# followLineMain.net
KiCad netlist of a schematic drawn in EAGLE
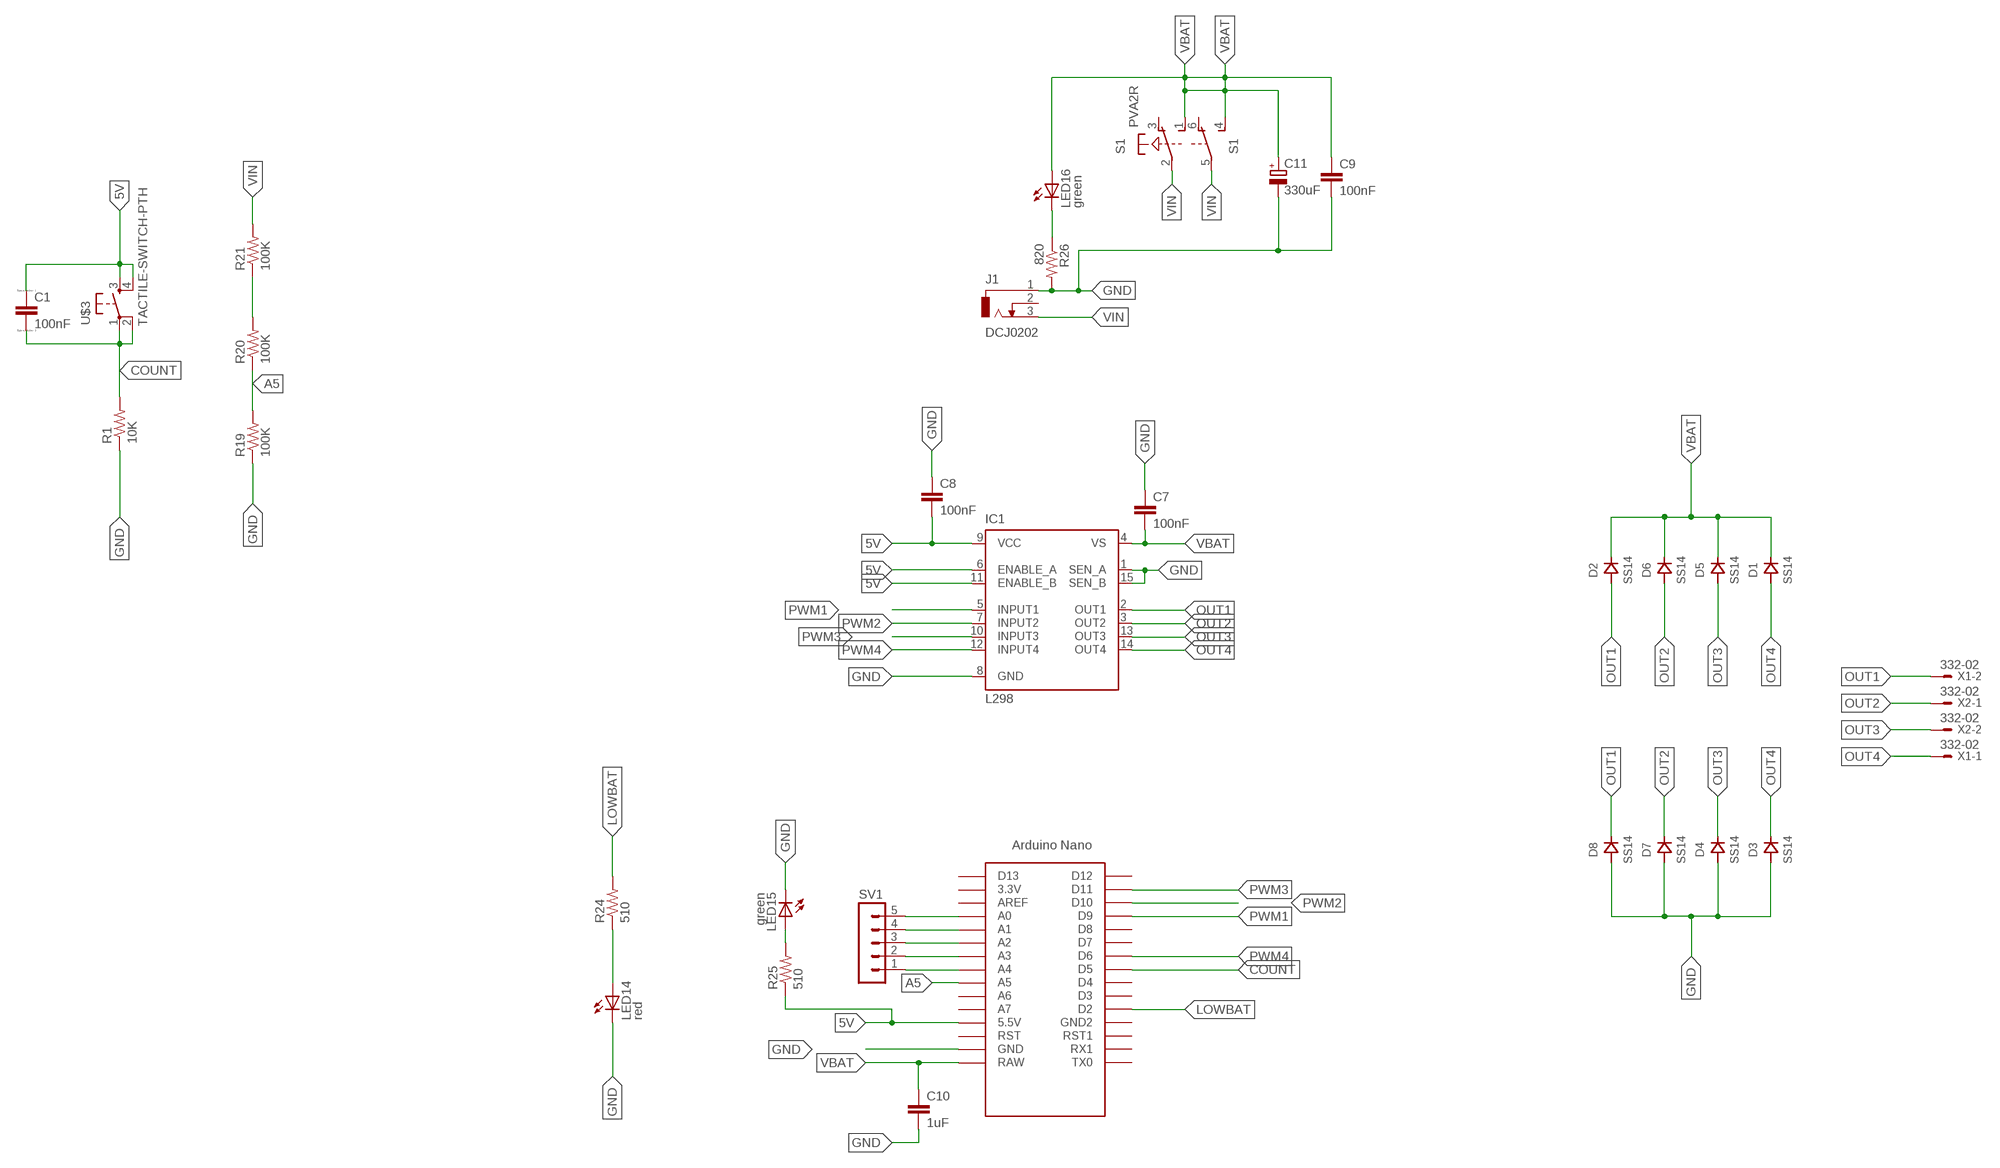
[diagram p0: schematic, sheet 1]

(export (version "E")
  (design (tool "Eeschema 10.0.6"))
  (components
    (comp (ref "C1")
      (value "100nF")
      (footprint "eagle-import:C0603")
      (libsource (lib "eagle-import") (part "CC0603"))
    )
    (comp (ref "C7")
      (value "100nF")
      (footprint "eagle-import:0805")
      (libsource (lib "eagle-import") (part "CAP0805"))
    )
    (comp (ref "C8")
      (value "100nF")
      (footprint "eagle-import:0805")
      (libsource (lib "eagle-import") (part "CAP0805"))
    )
    (comp (ref "C9")
      (value "100nF")
      (footprint "eagle-import:0805")
      (libsource (lib "eagle-import") (part "CAP0805"))
    )
    (comp (ref "C10")
      (value "1uF")
      (footprint "eagle-import:1206")
      (libsource (lib "eagle-import") (part "CAP1206"))
    )
    (comp (ref "C11")
      (value "330uF")
      (footprint "eagle-import:E5-13")
      (libsource (lib "eagle-import") (part "CPOL-EUE5-13"))
    )
    (comp (ref "D1")
      (value "SS14")
      (footprint "eagle-import:DO214")
      (libsource (lib "eagle-import") (part "SS14"))
    )
    (comp (ref "D2")
      (value "SS14")
      (footprint "eagle-import:DO214")
      (libsource (lib "eagle-import") (part "SS14"))
    )
    (comp (ref "D3")
      (value "SS14")
      (footprint "eagle-import:DO214")
      (libsource (lib "eagle-import") (part "SS14"))
    )
    (comp (ref "D4")
      (value "SS14")
      (footprint "eagle-import:DO214")
      (libsource (lib "eagle-import") (part "SS14"))
    )
    (comp (ref "D5")
      (value "SS14")
      (footprint "eagle-import:DO214")
      (libsource (lib "eagle-import") (part "SS14"))
    )
    (comp (ref "D6")
      (value "SS14")
      (footprint "eagle-import:DO214")
      (libsource (lib "eagle-import") (part "SS14"))
    )
    (comp (ref "D7")
      (value "SS14")
      (footprint "eagle-import:DO214")
      (libsource (lib "eagle-import") (part "SS14"))
    )
    (comp (ref "D8")
      (value "SS14")
      (footprint "eagle-import:DO214")
      (libsource (lib "eagle-import") (part "SS14"))
    )
    (comp (ref "IC1")
      (value "L298")
      (footprint "eagle-import:MULTIWATT-15")
      (fields (field (name "MPN") "L298N"))
      (libsource (lib "eagle-import") (part "L298"))
    )
    (comp (ref "J1")
      (value "DCJ0202")
      (footprint "eagle-import:DCJ0202")
      (libsource (lib "eagle-import") (part "DCJ0202"))
    )
    (comp (ref "LED14")
      (value "red")
      (footprint "eagle-import:SML0805")
      (libsource (lib "eagle-import") (part "LEDSML0805"))
    )
    (comp (ref "LED15")
      (value "green")
      (footprint "eagle-import:SML0805")
      (libsource (lib "eagle-import") (part "LEDSML0805"))
    )
    (comp (ref "LED16")
      (value "green")
      (footprint "eagle-import:SML0805")
      (libsource (lib "eagle-import") (part "LEDSML0805"))
    )
    (comp (ref "R1")
      (value "10K")
      (footprint "eagle-import:0805")
      (libsource (lib "eagle-import") (part "RESISTOR0805-RES"))
    )
    (comp (ref "R19")
      (value "100K")
      (footprint "eagle-import:0805")
      (libsource (lib "eagle-import") (part "RESISTOR0805-RES"))
    )
    (comp (ref "R20")
      (value "100K")
      (footprint "eagle-import:0805")
      (libsource (lib "eagle-import") (part "RESISTOR0805-RES"))
    )
    (comp (ref "R21")
      (value "100K")
      (footprint "eagle-import:0805")
      (libsource (lib "eagle-import") (part "RESISTOR0805-RES"))
    )
    (comp (ref "R24")
      (value "510")
      (footprint "eagle-import:0805")
      (libsource (lib "eagle-import") (part "RESISTOR0805-RES"))
    )
    (comp (ref "R25")
      (value "510")
      (footprint "eagle-import:0805")
      (libsource (lib "eagle-import") (part "RESISTOR0805-RES"))
    )
    (comp (ref "R26")
      (value "820")
      (footprint "eagle-import:0805")
      (libsource (lib "eagle-import") (part "RESISTOR0805-RES"))
    )
    (comp (ref "S1")
      (value "PVA2R")
      (footprint "eagle-import:PVA2R")
      (libsource (lib "eagle-import") (part "PVA2R"))
    )
    (comp (ref "SV1")
      (value "MA05-1")
      (footprint "eagle-import:MA05-1")
      (libsource (lib "eagle-import") (part "MA05-1"))
    )
    (comp (ref "U$1")
      (value "NANO")
      (footprint "eagle-import:NANO")
      (libsource (lib "eagle-import") (part "NANO"))
    )
    (comp (ref "U$3")
      (value "TACTILE-SWITCH-PTH")
      (footprint "eagle-import:TAC-SWITCH-PTH")
      (libsource (lib "eagle-import") (part "TACTILE-SWITCH-PTH"))
    )
    (comp (ref "X1")
      (value "332-02")
      (footprint "eagle-import:332-02")
      (libsource (lib "eagle-import") (part "332-02"))
    )
    (comp (ref "X2")
      (value "332-02")
      (footprint "eagle-import:332-02")
      (libsource (lib "eagle-import") (part "332-02"))
    )
  )
  (nets
    (net (code "1") (name "5V") (class "Default")
      (node (ref "C1") (pin "1") (pinfunction "1_1") (pintype "passive"))
      (node (ref "C8") (pin "2") (pinfunction "2_2") (pintype "passive"))
      (node (ref "IC1") (pin "11") (pinfunction "ENABLE_B_11") (pintype "input"))
      (node (ref "IC1") (pin "6") (pinfunction "ENABLE_A_6") (pintype "input"))
      (node (ref "IC1") (pin "9") (pinfunction "VCC_9") (pintype "power_in"))
      (node (ref "R25") (pin "1") (pinfunction "1_1") (pintype "passive"))
      (node (ref "U$1") (pin "5V") (pinfunction "5.5V_5V") (pintype "bidirectional"))
      (node (ref "U$3") (pin "3") (pinfunction "3_3") (pintype "passive"))
      (node (ref "U$3") (pin "4") (pinfunction "4_4") (pintype "passive"))
    )
    (net (code "2") (name "A5") (class "Default")
      (node (ref "R19") (pin "2") (pinfunction "2_2") (pintype "passive"))
      (node (ref "R20") (pin "1") (pinfunction "1_1") (pintype "passive"))
      (node (ref "U$1") (pin "A5") (pinfunction "A5_A5") (pintype "bidirectional"))
    )
    (net (code "3") (name "COUNT") (class "Default")
      (node (ref "C1") (pin "2") (pinfunction "2_2") (pintype "passive"))
      (node (ref "R1") (pin "2") (pinfunction "2_2") (pintype "passive"))
      (node (ref "U$1") (pin "D5") (pinfunction "D5_D5") (pintype "bidirectional"))
      (node (ref "U$3") (pin "1") (pinfunction "1_1") (pintype "passive"))
      (node (ref "U$3") (pin "2") (pinfunction "2_2") (pintype "passive"))
    )
    (net (code "4") (name "GND") (class "Default")
      (node (ref "C10") (pin "2") (pinfunction "2_2") (pintype "passive"))
      (node (ref "C11") (pin "-") (pinfunction "-_-") (pintype "passive"))
      (node (ref "C7") (pin "1") (pinfunction "1_1") (pintype "passive"))
      (node (ref "C8") (pin "1") (pinfunction "1_1") (pintype "passive"))
      (node (ref "C9") (pin "2") (pinfunction "2_2") (pintype "passive"))
      (node (ref "D3") (pin "ANODE") (pinfunction "ANODE_ANODE") (pintype "bidirectional"))
      (node (ref "D4") (pin "ANODE") (pinfunction "ANODE_ANODE") (pintype "bidirectional"))
      (node (ref "D7") (pin "ANODE") (pinfunction "ANODE_ANODE") (pintype "bidirectional"))
      (node (ref "D8") (pin "ANODE") (pinfunction "ANODE_ANODE") (pintype "bidirectional"))
      (node (ref "IC1") (pin "1") (pinfunction "SEN_A_1") (pintype "input"))
      (node (ref "IC1") (pin "15") (pinfunction "SEN_B_15") (pintype "input"))
      (node (ref "IC1") (pin "8") (pinfunction "GND_8") (pintype "power_in"))
      (node (ref "J1") (pin "1") (pinfunction "1_1") (pintype "passive"))
      (node (ref "LED14") (pin "C") (pinfunction "C_C") (pintype "passive"))
      (node (ref "LED15") (pin "C") (pinfunction "C_C") (pintype "passive"))
      (node (ref "R1") (pin "1") (pinfunction "1_1") (pintype "passive"))
      (node (ref "R19") (pin "1") (pinfunction "1_1") (pintype "passive"))
      (node (ref "R26") (pin "2") (pinfunction "2_2") (pintype "passive"))
      (node (ref "U$1") (pin "GND") (pinfunction "GND_GND") (pintype "bidirectional"))
    )
    (net (code "5") (name "LOWBAT") (class "Default")
      (node (ref "R24") (pin "2") (pinfunction "2_2") (pintype "passive"))
      (node (ref "U$1") (pin "D2") (pinfunction "D2_D2") (pintype "bidirectional"))
    )
    (net (code "6") (name "Net-(LED14-PadA)") (class "Default")
      (node (ref "LED14") (pin "A") (pinfunction "A_A") (pintype "passive"))
      (node (ref "R24") (pin "1") (pinfunction "1_1") (pintype "passive"))
    )
    (net (code "7") (name "Net-(LED15-PadA)") (class "Default")
      (node (ref "LED15") (pin "A") (pinfunction "A_A") (pintype "passive"))
      (node (ref "R25") (pin "2") (pinfunction "2_2") (pintype "passive"))
    )
    (net (code "8") (name "Net-(LED16-PadC)") (class "Default")
      (node (ref "LED16") (pin "C") (pinfunction "C_C") (pintype "passive"))
      (node (ref "R26") (pin "1") (pinfunction "1_1") (pintype "passive"))
    )
    (net (code "9") (name "Net-(R20-Pad2)") (class "Default")
      (node (ref "R20") (pin "2") (pinfunction "2_2") (pintype "passive"))
      (node (ref "R21") (pin "1") (pinfunction "1_1") (pintype "passive"))
    )
    (net (code "10") (name "Net-(SV1-Pad1)") (class "Default")
      (node (ref "SV1") (pin "1") (pinfunction "1_1") (pintype "passive"))
      (node (ref "U$1") (pin "A4") (pinfunction "A4_A4") (pintype "bidirectional"))
    )
    (net (code "11") (name "Net-(SV1-Pad2)") (class "Default")
      (node (ref "SV1") (pin "2") (pinfunction "2_2") (pintype "passive"))
      (node (ref "U$1") (pin "A3") (pinfunction "A3_A3") (pintype "bidirectional"))
    )
    (net (code "12") (name "Net-(SV1-Pad3)") (class "Default")
      (node (ref "SV1") (pin "3") (pinfunction "3_3") (pintype "passive"))
      (node (ref "U$1") (pin "A2") (pinfunction "A2_A2") (pintype "bidirectional"))
    )
    (net (code "13") (name "Net-(SV1-Pad4)") (class "Default")
      (node (ref "SV1") (pin "4") (pinfunction "4_4") (pintype "passive"))
      (node (ref "U$1") (pin "A1") (pinfunction "A1_A1") (pintype "bidirectional"))
    )
    (net (code "14") (name "Net-(SV1-Pad5)") (class "Default")
      (node (ref "SV1") (pin "5") (pinfunction "5_5") (pintype "passive"))
      (node (ref "U$1") (pin "A0") (pinfunction "A0_A0") (pintype "bidirectional"))
    )
    (net (code "15") (name "OUT1") (class "Default")
      (node (ref "D2") (pin "ANODE") (pinfunction "ANODE_ANODE") (pintype "bidirectional"))
      (node (ref "D8") (pin "CATHODE") (pinfunction "CATHODE_CATHODE") (pintype "bidirectional"))
      (node (ref "IC1") (pin "2") (pinfunction "OUT1_2") (pintype "output"))
      (node (ref "X1") (pin "2") (pinfunction "S_2") (pintype "passive"))
    )
    (net (code "16") (name "OUT2") (class "Default")
      (node (ref "D6") (pin "ANODE") (pinfunction "ANODE_ANODE") (pintype "bidirectional"))
      (node (ref "D7") (pin "CATHODE") (pinfunction "CATHODE_CATHODE") (pintype "bidirectional"))
      (node (ref "IC1") (pin "3") (pinfunction "OUT2_3") (pintype "output"))
      (node (ref "X2") (pin "1") (pinfunction "S_1") (pintype "passive"))
    )
    (net (code "17") (name "OUT3") (class "Default")
      (node (ref "D4") (pin "CATHODE") (pinfunction "CATHODE_CATHODE") (pintype "bidirectional"))
      (node (ref "D5") (pin "ANODE") (pinfunction "ANODE_ANODE") (pintype "bidirectional"))
      (node (ref "IC1") (pin "13") (pinfunction "OUT3_13") (pintype "output"))
      (node (ref "X2") (pin "2") (pinfunction "S_2") (pintype "passive"))
    )
    (net (code "18") (name "OUT4") (class "Default")
      (node (ref "D1") (pin "ANODE") (pinfunction "ANODE_ANODE") (pintype "bidirectional"))
      (node (ref "D3") (pin "CATHODE") (pinfunction "CATHODE_CATHODE") (pintype "bidirectional"))
      (node (ref "IC1") (pin "14") (pinfunction "OUT4_14") (pintype "output"))
      (node (ref "X1") (pin "1") (pinfunction "S_1") (pintype "passive"))
    )
    (net (code "19") (name "PWM1") (class "Default")
      (node (ref "IC1") (pin "5") (pinfunction "INPUT1_5") (pintype "input"))
      (node (ref "U$1") (pin "D9") (pinfunction "D9_D9") (pintype "bidirectional"))
    )
    (net (code "20") (name "PWM2") (class "Default")
      (node (ref "IC1") (pin "7") (pinfunction "INPUT2_7") (pintype "input"))
      (node (ref "U$1") (pin "D10") (pinfunction "D10_D10") (pintype "bidirectional"))
    )
    (net (code "21") (name "PWM3") (class "Default")
      (node (ref "IC1") (pin "10") (pinfunction "INPUT3_10") (pintype "input"))
      (node (ref "U$1") (pin "D11") (pinfunction "D11_D11") (pintype "bidirectional"))
    )
    (net (code "22") (name "PWM4") (class "Default")
      (node (ref "IC1") (pin "12") (pinfunction "INPUT4_12") (pintype "input"))
      (node (ref "U$1") (pin "D6") (pinfunction "D6_D6") (pintype "bidirectional"))
    )
    (net (code "23") (name "VBAT") (class "Default")
      (node (ref "C10") (pin "1") (pinfunction "1_1") (pintype "passive"))
      (node (ref "C11") (pin "+") (pinfunction "+_+") (pintype "passive"))
      (node (ref "C7") (pin "2") (pinfunction "2_2") (pintype "passive"))
      (node (ref "C9") (pin "1") (pinfunction "1_1") (pintype "passive"))
      (node (ref "D1") (pin "CATHODE") (pinfunction "CATHODE_CATHODE") (pintype "bidirectional"))
      (node (ref "D2") (pin "CATHODE") (pinfunction "CATHODE_CATHODE") (pintype "bidirectional"))
      (node (ref "D5") (pin "CATHODE") (pinfunction "CATHODE_CATHODE") (pintype "bidirectional"))
      (node (ref "D6") (pin "CATHODE") (pinfunction "CATHODE_CATHODE") (pintype "bidirectional"))
      (node (ref "IC1") (pin "4") (pinfunction "VS_4") (pintype "power_in"))
      (node (ref "LED16") (pin "A") (pinfunction "A_A") (pintype "passive"))
      (node (ref "S1") (pin "1") (pinfunction "S_1") (pintype "passive"))
      (node (ref "S1") (pin "4") (pinfunction "S_4") (pintype "passive"))
      (node (ref "U$1") (pin "RAW") (pinfunction "RAW_RAW") (pintype "bidirectional"))
    )
    (net (code "24") (name "VIN") (class "Default")
      (node (ref "J1") (pin "3") (pinfunction "3_3") (pintype "passive"))
      (node (ref "R21") (pin "2") (pinfunction "2_2") (pintype "passive"))
      (node (ref "S1") (pin "2") (pinfunction "P_2") (pintype "passive"))
      (node (ref "S1") (pin "5") (pinfunction "P_5") (pintype "passive"))
    )
    (net (code "25") (name "unconnected-(J1-Pad2)") (class "Default")
      (node (ref "J1") (pin "2") (pinfunction "2_2") (pintype "passive"))
    )
    (net (code "26") (name "unconnected-(S1A-O-Pad3)") (class "Default")
      (node (ref "S1") (pin "3") (pinfunction "O_3") (pintype "passive"))
    )
    (net (code "27") (name "unconnected-(S1B-O-Pad6)") (class "Default")
      (node (ref "S1") (pin "6") (pinfunction "O_6") (pintype "passive"))
    )
    (net (code "28") (name "unconnected-(U$1-GND2-PadGND1)") (class "Default")
      (node (ref "U$1") (pin "GND1") (pinfunction "GND2_GND1") (pintype "bidirectional"))
    )
    (net (code "29") (name "unconnected-(U$1-Pad3.3V)") (class "Default")
      (node (ref "U$1") (pin "3.3V") (pinfunction "3.3V_3.3V") (pintype "bidirectional"))
    )
    (net (code "30") (name "unconnected-(U$1-PadA6)") (class "Default")
      (node (ref "U$1") (pin "A6") (pinfunction "A6_A6") (pintype "bidirectional"))
    )
    (net (code "31") (name "unconnected-(U$1-PadA7)") (class "Default")
      (node (ref "U$1") (pin "A7") (pinfunction "A7_A7") (pintype "bidirectional"))
    )
    (net (code "32") (name "unconnected-(U$1-PadAREF)") (class "Default")
      (node (ref "U$1") (pin "AREF") (pinfunction "AREF_AREF") (pintype "bidirectional"))
    )
    (net (code "33") (name "unconnected-(U$1-PadD3)") (class "Default")
      (node (ref "U$1") (pin "D3") (pinfunction "D3_D3") (pintype "bidirectional"))
    )
    (net (code "34") (name "unconnected-(U$1-PadD4)") (class "Default")
      (node (ref "U$1") (pin "D4") (pinfunction "D4_D4") (pintype "bidirectional"))
    )
    (net (code "35") (name "unconnected-(U$1-PadD7)") (class "Default")
      (node (ref "U$1") (pin "D7") (pinfunction "D7_D7") (pintype "bidirectional"))
    )
    (net (code "36") (name "unconnected-(U$1-PadD8)") (class "Default")
      (node (ref "U$1") (pin "D8") (pinfunction "D8_D8") (pintype "bidirectional"))
    )
    (net (code "37") (name "unconnected-(U$1-PadD12)") (class "Default")
      (node (ref "U$1") (pin "D12") (pinfunction "D12_D12") (pintype "bidirectional"))
    )
    (net (code "38") (name "unconnected-(U$1-PadD13)") (class "Default")
      (node (ref "U$1") (pin "D13") (pinfunction "D13_D13") (pintype "bidirectional"))
    )
    (net (code "39") (name "unconnected-(U$1-PadICSP1)") (class "Default")
      (node (ref "U$1") (pin "ICSP1") (pinfunction "ICSP1_ICSP1") (pintype "bidirectional"))
    )
    (net (code "40") (name "unconnected-(U$1-PadICSP2)") (class "Default")
      (node (ref "U$1") (pin "ICSP2") (pinfunction "ICSP2_ICSP2") (pintype "bidirectional"))
    )
    (net (code "41") (name "unconnected-(U$1-PadICSP3)") (class "Default")
      (node (ref "U$1") (pin "ICSP3") (pinfunction "ICSP3_ICSP3") (pintype "bidirectional"))
    )
    (net (code "42") (name "unconnected-(U$1-PadICSP4)") (class "Default")
      (node (ref "U$1") (pin "ICSP4") (pinfunction "ICSP4_ICSP4") (pintype "bidirectional"))
    )
    (net (code "43") (name "unconnected-(U$1-PadICSP5)") (class "Default")
      (node (ref "U$1") (pin "ICSP5") (pinfunction "ICSP5_ICSP5") (pintype "bidirectional"))
    )
    (net (code "44") (name "unconnected-(U$1-PadICSP6)") (class "Default")
      (node (ref "U$1") (pin "ICSP6") (pinfunction "ICSP6_ICSP6") (pintype "bidirectional"))
    )
    (net (code "45") (name "unconnected-(U$1-PadRST)") (class "Default")
      (node (ref "U$1") (pin "RST") (pinfunction "RST_RST") (pintype "bidirectional"))
    )
    (net (code "46") (name "unconnected-(U$1-PadRST1)") (class "Default")
      (node (ref "U$1") (pin "RST1") (pinfunction "RST1_RST1") (pintype "bidirectional"))
    )
    (net (code "47") (name "unconnected-(U$1-PadRX1)") (class "Default")
      (node (ref "U$1") (pin "RX1") (pinfunction "RX1_RX1") (pintype "bidirectional"))
    )
    (net (code "48") (name "unconnected-(U$1-PadTX0)") (class "Default")
      (node (ref "U$1") (pin "TX0") (pinfunction "TX0_TX0") (pintype "bidirectional"))
    )
  )
)
